# Debug_FeatherWing.net
KiCad netlist of a schematic drawn in EAGLE
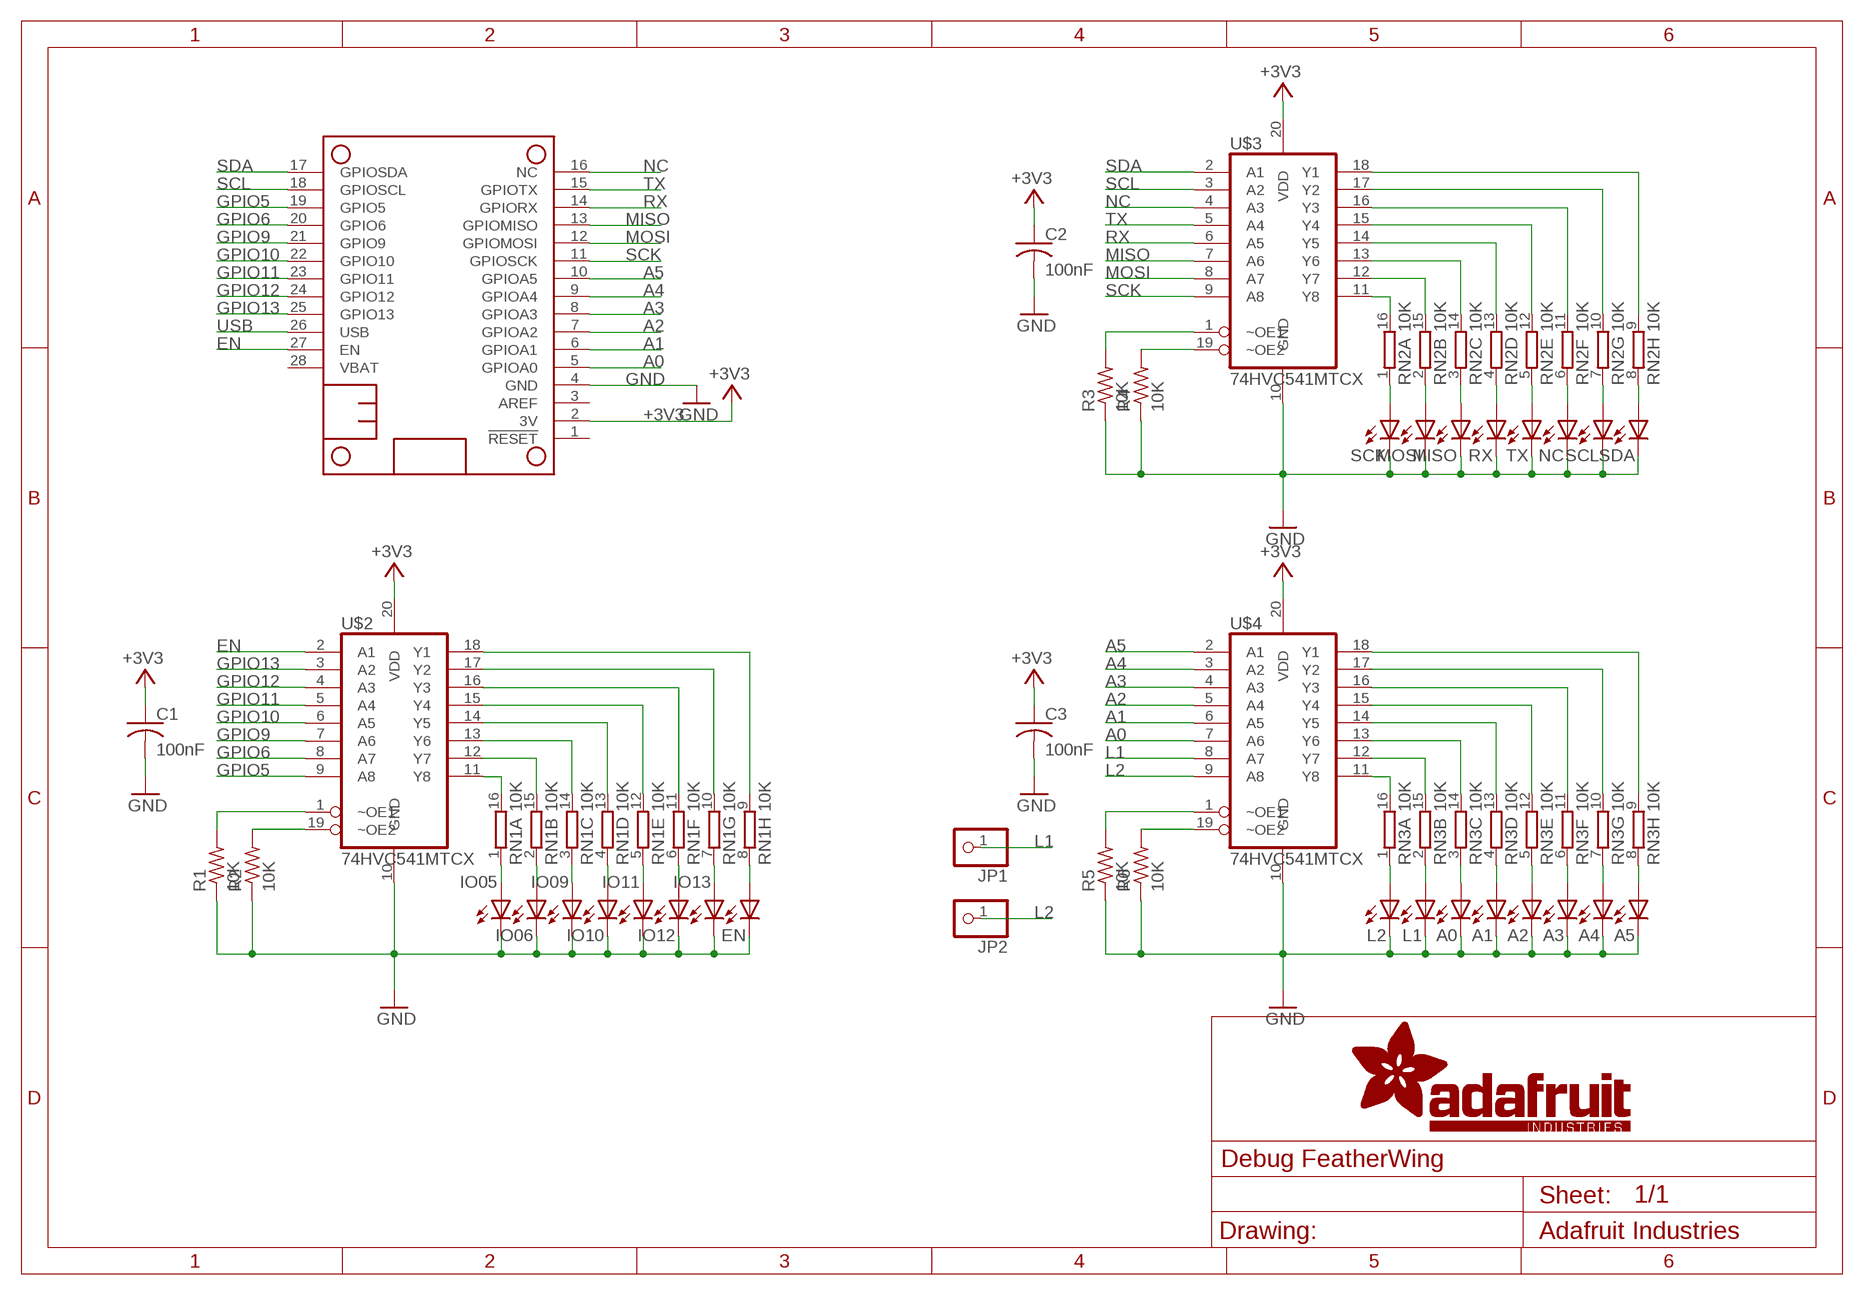
[diagram p0: schematic, sheet 1]

(export (version "E")
  (design (tool "Eeschema 10.0.6"))
  (components
    (comp (ref "A0")
      (value "Green")
      (footprint "eagle-import:CHIPLED_0805")
      (libsource (lib "eagle-import") (part "LEDCHIPLED_0805"))
    )
    (comp (ref "A1")
      (value "Green")
      (footprint "eagle-import:CHIPLED_0805")
      (libsource (lib "eagle-import") (part "LEDCHIPLED_0805"))
    )
    (comp (ref "A2")
      (value "Green")
      (footprint "eagle-import:CHIPLED_0805")
      (libsource (lib "eagle-import") (part "LEDCHIPLED_0805"))
    )
    (comp (ref "A3")
      (value "Green")
      (footprint "eagle-import:CHIPLED_0805")
      (libsource (lib "eagle-import") (part "LEDCHIPLED_0805"))
    )
    (comp (ref "A4")
      (value "Green")
      (footprint "eagle-import:CHIPLED_0805")
      (libsource (lib "eagle-import") (part "LEDCHIPLED_0805"))
    )
    (comp (ref "A5")
      (value "Green")
      (footprint "eagle-import:CHIPLED_0805")
      (libsource (lib "eagle-import") (part "LEDCHIPLED_0805"))
    )
    (comp (ref "C1")
      (value "100nF")
      (footprint "eagle-import:C0805")
      (libsource (lib "eagle-import") (part "C-USC0805"))
    )
    (comp (ref "C2")
      (value "100nF")
      (footprint "eagle-import:C0805")
      (libsource (lib "eagle-import") (part "C-USC0805"))
    )
    (comp (ref "C3")
      (value "100nF")
      (footprint "eagle-import:C0805")
      (libsource (lib "eagle-import") (part "C-USC0805"))
    )
    (comp (ref "EN")
      (value "Green")
      (footprint "eagle-import:CHIPLED_0805")
      (libsource (lib "eagle-import") (part "LEDCHIPLED_0805"))
    )
    (comp (ref "IO05")
      (value "Green")
      (footprint "eagle-import:CHIPLED_0805")
      (libsource (lib "eagle-import") (part "LEDCHIPLED_0805"))
    )
    (comp (ref "IO06")
      (value "Green")
      (footprint "eagle-import:CHIPLED_0805")
      (libsource (lib "eagle-import") (part "LEDCHIPLED_0805"))
    )
    (comp (ref "IO09")
      (value "Green")
      (footprint "eagle-import:CHIPLED_0805")
      (libsource (lib "eagle-import") (part "LEDCHIPLED_0805"))
    )
    (comp (ref "IO10")
      (value "Green")
      (footprint "eagle-import:CHIPLED_0805")
      (libsource (lib "eagle-import") (part "LEDCHIPLED_0805"))
    )
    (comp (ref "IO11")
      (value "Green")
      (footprint "eagle-import:CHIPLED_0805")
      (libsource (lib "eagle-import") (part "LEDCHIPLED_0805"))
    )
    (comp (ref "IO12")
      (value "Green")
      (footprint "eagle-import:CHIPLED_0805")
      (libsource (lib "eagle-import") (part "LEDCHIPLED_0805"))
    )
    (comp (ref "IO13")
      (value "Green")
      (footprint "eagle-import:CHIPLED_0805")
      (libsource (lib "eagle-import") (part "LEDCHIPLED_0805"))
    )
    (comp (ref "JP1")
      (value "PINHD-1X1")
      (footprint "eagle-import:1X01")
      (libsource (lib "eagle-import") (part "PINHD-1X1"))
    )
    (comp (ref "JP2")
      (value "PINHD-1X1")
      (footprint "eagle-import:1X01")
      (libsource (lib "eagle-import") (part "PINHD-1X1"))
    )
    (comp (ref "L1")
      (value "Green")
      (footprint "eagle-import:CHIPLED_0805")
      (libsource (lib "eagle-import") (part "LEDCHIPLED_0805"))
    )
    (comp (ref "L2")
      (value "Green")
      (footprint "eagle-import:CHIPLED_0805")
      (libsource (lib "eagle-import") (part "LEDCHIPLED_0805"))
    )
    (comp (ref "MISO")
      (value "Green")
      (footprint "eagle-import:CHIPLED_0805")
      (libsource (lib "eagle-import") (part "LEDCHIPLED_0805"))
    )
    (comp (ref "MOSI")
      (value "Green")
      (footprint "eagle-import:CHIPLED_0805")
      (libsource (lib "eagle-import") (part "LEDCHIPLED_0805"))
    )
    (comp (ref "MS1")
      (value "FEATHERWING")
      (footprint "eagle-import:FEATHERWING")
      (libsource (lib "eagle-import") (part "FEATHERWING"))
    )
    (comp (ref "NC")
      (value "Green")
      (footprint "eagle-import:CHIPLED_0805")
      (libsource (lib "eagle-import") (part "LEDCHIPLED_0805"))
    )
    (comp (ref "R1")
      (value "10K")
      (footprint "eagle-import:R0805")
      (libsource (lib "eagle-import") (part "R-US_R0805"))
    )
    (comp (ref "R2")
      (value "10K")
      (footprint "eagle-import:R0805")
      (libsource (lib "eagle-import") (part "R-US_R0805"))
    )
    (comp (ref "R3")
      (value "10K")
      (footprint "eagle-import:R0805")
      (libsource (lib "eagle-import") (part "R-US_R0805"))
    )
    (comp (ref "R4")
      (value "10K")
      (footprint "eagle-import:R0805")
      (libsource (lib "eagle-import") (part "R-US_R0805"))
    )
    (comp (ref "R5")
      (value "10K")
      (footprint "eagle-import:R0805")
      (libsource (lib "eagle-import") (part "R-US_R0805"))
    )
    (comp (ref "R6")
      (value "10K")
      (footprint "eagle-import:R0805")
      (libsource (lib "eagle-import") (part "R-US_R0805"))
    )
    (comp (ref "RN1")
      (value "10K")
      (footprint "eagle-import:EXB2HV")
      (libsource (lib "eagle-import") (part "8R-NEXB2HV"))
    )
    (comp (ref "RN2")
      (value "10K")
      (footprint "eagle-import:EXB2HV")
      (libsource (lib "eagle-import") (part "8R-NEXB2HV"))
    )
    (comp (ref "RN3")
      (value "10K")
      (footprint "eagle-import:EXB2HV")
      (libsource (lib "eagle-import") (part "8R-NEXB2HV"))
    )
    (comp (ref "RX")
      (value "Green")
      (footprint "eagle-import:CHIPLED_0805")
      (libsource (lib "eagle-import") (part "LEDCHIPLED_0805"))
    )
    (comp (ref "SCK")
      (value "Green")
      (footprint "eagle-import:CHIPLED_0805")
      (libsource (lib "eagle-import") (part "LEDCHIPLED_0805"))
    )
    (comp (ref "SCL")
      (value "Green")
      (footprint "eagle-import:CHIPLED_0805")
      (libsource (lib "eagle-import") (part "LEDCHIPLED_0805"))
    )
    (comp (ref "SDA")
      (value "Green")
      (footprint "eagle-import:CHIPLED_0805")
      (libsource (lib "eagle-import") (part "LEDCHIPLED_0805"))
    )
    (comp (ref "TX")
      (value "Green")
      (footprint "eagle-import:CHIPLED_0805")
      (libsource (lib "eagle-import") (part "LEDCHIPLED_0805"))
    )
    (comp (ref "U$2")
      (value "74HVC541MTCX")
      (footprint "eagle-import:TSSOP20")
      (libsource (lib "eagle-import") (part "74HVC541MTCX"))
    )
    (comp (ref "U$3")
      (value "74HVC541MTCX")
      (footprint "eagle-import:TSSOP20")
      (libsource (lib "eagle-import") (part "74HVC541MTCX"))
    )
    (comp (ref "U$4")
      (value "74HVC541MTCX")
      (footprint "eagle-import:TSSOP20")
      (libsource (lib "eagle-import") (part "74HVC541MTCX"))
    )
  )
  (nets
    (net (code "1") (name "+3V3") (class "Default")
      (node (ref "C1") (pin "1") (pinfunction "1_1") (pintype "passive"))
      (node (ref "C2") (pin "1") (pinfunction "1_1") (pintype "passive"))
      (node (ref "C3") (pin "1") (pinfunction "1_1") (pintype "passive"))
      (node (ref "MS1") (pin "2") (pinfunction "3V_2") (pintype "power_in"))
      (node (ref "U$2") (pin "20") (pinfunction "VDD_20") (pintype "power_in"))
      (node (ref "U$3") (pin "20") (pinfunction "VDD_20") (pintype "power_in"))
      (node (ref "U$4") (pin "20") (pinfunction "VDD_20") (pintype "power_in"))
    )
    (net (code "2") (name "/A0") (class "Default")
      (node (ref "MS1") (pin "5") (pinfunction "GPIOA0_5") (pintype "bidirectional"))
      (node (ref "U$4") (pin "7") (pinfunction "A6_7") (pintype "input"))
    )
    (net (code "3") (name "/A1") (class "Default")
      (node (ref "MS1") (pin "6") (pinfunction "GPIOA1_6") (pintype "bidirectional"))
      (node (ref "U$4") (pin "6") (pinfunction "A5_6") (pintype "input"))
    )
    (net (code "4") (name "/A2") (class "Default")
      (node (ref "MS1") (pin "7") (pinfunction "GPIOA2_7") (pintype "bidirectional"))
      (node (ref "U$4") (pin "5") (pinfunction "A4_5") (pintype "input"))
    )
    (net (code "5") (name "/A3") (class "Default")
      (node (ref "MS1") (pin "8") (pinfunction "GPIOA3_8") (pintype "bidirectional"))
      (node (ref "U$4") (pin "4") (pinfunction "A3_4") (pintype "input"))
    )
    (net (code "6") (name "/A4") (class "Default")
      (node (ref "MS1") (pin "9") (pinfunction "GPIOA4_9") (pintype "bidirectional"))
      (node (ref "U$4") (pin "3") (pinfunction "A2_3") (pintype "input"))
    )
    (net (code "7") (name "/A5") (class "Default")
      (node (ref "MS1") (pin "10") (pinfunction "GPIOA5_10") (pintype "bidirectional"))
      (node (ref "U$4") (pin "2") (pinfunction "A1_2") (pintype "input"))
    )
    (net (code "8") (name "/EN") (class "Default")
      (node (ref "MS1") (pin "27") (pinfunction "EN_27") (pintype "passive"))
      (node (ref "U$2") (pin "2") (pinfunction "A1_2") (pintype "input"))
    )
    (net (code "9") (name "/GPIO5") (class "Default")
      (node (ref "MS1") (pin "19") (pinfunction "GPIO5_19") (pintype "bidirectional"))
      (node (ref "U$2") (pin "9") (pinfunction "A8_9") (pintype "input"))
    )
    (net (code "10") (name "/GPIO6") (class "Default")
      (node (ref "MS1") (pin "20") (pinfunction "GPIO6_20") (pintype "bidirectional"))
      (node (ref "U$2") (pin "8") (pinfunction "A7_8") (pintype "input"))
    )
    (net (code "11") (name "/GPIO9") (class "Default")
      (node (ref "MS1") (pin "21") (pinfunction "GPIO9_21") (pintype "bidirectional"))
      (node (ref "U$2") (pin "7") (pinfunction "A6_7") (pintype "input"))
    )
    (net (code "12") (name "/GPIO10") (class "Default")
      (node (ref "MS1") (pin "22") (pinfunction "GPIO10_22") (pintype "bidirectional"))
      (node (ref "U$2") (pin "6") (pinfunction "A5_6") (pintype "input"))
    )
    (net (code "13") (name "/GPIO11") (class "Default")
      (node (ref "MS1") (pin "23") (pinfunction "GPIO11_23") (pintype "bidirectional"))
      (node (ref "U$2") (pin "5") (pinfunction "A4_5") (pintype "input"))
    )
    (net (code "14") (name "/GPIO12") (class "Default")
      (node (ref "MS1") (pin "24") (pinfunction "GPIO12_24") (pintype "bidirectional"))
      (node (ref "U$2") (pin "4") (pinfunction "A3_4") (pintype "input"))
    )
    (net (code "15") (name "/GPIO13") (class "Default")
      (node (ref "MS1") (pin "25") (pinfunction "GPIO13_25") (pintype "bidirectional"))
      (node (ref "U$2") (pin "3") (pinfunction "A2_3") (pintype "input"))
    )
    (net (code "16") (name "/L1") (class "Default")
      (node (ref "JP1") (pin "1") (pinfunction "1_1") (pintype "passive"))
      (node (ref "U$4") (pin "8") (pinfunction "A7_8") (pintype "input"))
    )
    (net (code "17") (name "/L2") (class "Default")
      (node (ref "JP2") (pin "1") (pinfunction "1_1") (pintype "passive"))
      (node (ref "U$4") (pin "9") (pinfunction "A8_9") (pintype "input"))
    )
    (net (code "18") (name "/MISO") (class "Default")
      (node (ref "MS1") (pin "13") (pinfunction "GPIOMISO_13") (pintype "bidirectional"))
      (node (ref "U$3") (pin "7") (pinfunction "A6_7") (pintype "input"))
    )
    (net (code "19") (name "/MOSI") (class "Default")
      (node (ref "MS1") (pin "12") (pinfunction "GPIOMOSI_12") (pintype "bidirectional"))
      (node (ref "U$3") (pin "8") (pinfunction "A7_8") (pintype "input"))
    )
    (net (code "20") (name "/NC") (class "Default")
      (node (ref "MS1") (pin "16") (pinfunction "NC_16") (pintype "passive"))
      (node (ref "U$3") (pin "4") (pinfunction "A3_4") (pintype "input"))
    )
    (net (code "21") (name "/RX") (class "Default")
      (node (ref "MS1") (pin "14") (pinfunction "GPIORX_14") (pintype "bidirectional"))
      (node (ref "U$3") (pin "6") (pinfunction "A5_6") (pintype "input"))
    )
    (net (code "22") (name "/SCK") (class "Default")
      (node (ref "MS1") (pin "11") (pinfunction "GPIOSCK_11") (pintype "bidirectional"))
      (node (ref "U$3") (pin "9") (pinfunction "A8_9") (pintype "input"))
    )
    (net (code "23") (name "/SCL") (class "Default")
      (node (ref "MS1") (pin "18") (pinfunction "GPIOSCL_18") (pintype "bidirectional"))
      (node (ref "U$3") (pin "3") (pinfunction "A2_3") (pintype "input"))
    )
    (net (code "24") (name "/SDA") (class "Default")
      (node (ref "MS1") (pin "17") (pinfunction "GPIOSDA_17") (pintype "bidirectional"))
      (node (ref "U$3") (pin "2") (pinfunction "A1_2") (pintype "input"))
    )
    (net (code "25") (name "/TX") (class "Default")
      (node (ref "MS1") (pin "15") (pinfunction "GPIOTX_15") (pintype "bidirectional"))
      (node (ref "U$3") (pin "5") (pinfunction "A4_5") (pintype "input"))
    )
    (net (code "26") (name "/USB") (class "Default")
      (node (ref "MS1") (pin "26") (pinfunction "USB_26") (pintype "power_in"))
    )
    (net (code "27") (name "/VBAT") (class "Default")
      (node (ref "MS1") (pin "28") (pinfunction "VBAT_28") (pintype "power_in"))
    )
    (net (code "28") (name "GND") (class "Default")
      (node (ref "A0") (pin "C") (pinfunction "C_C") (pintype "passive"))
      (node (ref "A1") (pin "C") (pinfunction "C_C") (pintype "passive"))
      (node (ref "A2") (pin "C") (pinfunction "C_C") (pintype "passive"))
      (node (ref "A3") (pin "C") (pinfunction "C_C") (pintype "passive"))
      (node (ref "A4") (pin "C") (pinfunction "C_C") (pintype "passive"))
      (node (ref "A5") (pin "C") (pinfunction "C_C") (pintype "passive"))
      (node (ref "C1") (pin "2") (pinfunction "2_2") (pintype "passive"))
      (node (ref "C2") (pin "2") (pinfunction "2_2") (pintype "passive"))
      (node (ref "C3") (pin "2") (pinfunction "2_2") (pintype "passive"))
      (node (ref "EN") (pin "C") (pinfunction "C_C") (pintype "passive"))
      (node (ref "IO05") (pin "C") (pinfunction "C_C") (pintype "passive"))
      (node (ref "IO06") (pin "C") (pinfunction "C_C") (pintype "passive"))
      (node (ref "IO09") (pin "C") (pinfunction "C_C") (pintype "passive"))
      (node (ref "IO10") (pin "C") (pinfunction "C_C") (pintype "passive"))
      (node (ref "IO11") (pin "C") (pinfunction "C_C") (pintype "passive"))
      (node (ref "IO12") (pin "C") (pinfunction "C_C") (pintype "passive"))
      (node (ref "IO13") (pin "C") (pinfunction "C_C") (pintype "passive"))
      (node (ref "L1") (pin "C") (pinfunction "C_C") (pintype "passive"))
      (node (ref "L2") (pin "C") (pinfunction "C_C") (pintype "passive"))
      (node (ref "MISO") (pin "C") (pinfunction "C_C") (pintype "passive"))
      (node (ref "MOSI") (pin "C") (pinfunction "C_C") (pintype "passive"))
      (node (ref "MS1") (pin "4") (pinfunction "GND_4") (pintype "power_in"))
      (node (ref "NC") (pin "C") (pinfunction "C_C") (pintype "passive"))
      (node (ref "R1") (pin "1") (pinfunction "1_1") (pintype "passive"))
      (node (ref "R2") (pin "1") (pinfunction "1_1") (pintype "passive"))
      (node (ref "R3") (pin "1") (pinfunction "1_1") (pintype "passive"))
      (node (ref "R4") (pin "1") (pinfunction "1_1") (pintype "passive"))
      (node (ref "R5") (pin "1") (pinfunction "1_1") (pintype "passive"))
      (node (ref "R6") (pin "1") (pinfunction "1_1") (pintype "passive"))
      (node (ref "RX") (pin "C") (pinfunction "C_C") (pintype "passive"))
      (node (ref "SCK") (pin "C") (pinfunction "C_C") (pintype "passive"))
      (node (ref "SCL") (pin "C") (pinfunction "C_C") (pintype "passive"))
      (node (ref "SDA") (pin "C") (pinfunction "C_C") (pintype "passive"))
      (node (ref "TX") (pin "C") (pinfunction "C_C") (pintype "passive"))
      (node (ref "U$2") (pin "10") (pinfunction "GND_10") (pintype "power_in"))
      (node (ref "U$3") (pin "10") (pinfunction "GND_10") (pintype "power_in"))
      (node (ref "U$4") (pin "10") (pinfunction "GND_10") (pintype "power_in"))
    )
    (net (code "29") (name "Net-(IO05-PadA)") (class "Default")
      (node (ref "IO05") (pin "A") (pinfunction "A_A") (pintype "passive"))
      (node (ref "RN1") (pin "1") (pinfunction "1_1") (pintype "passive"))
    )
    (net (code "30") (name "Net-(L2-PadA)") (class "Default")
      (node (ref "L2") (pin "A") (pinfunction "A_A") (pintype "passive"))
      (node (ref "RN3") (pin "1") (pinfunction "1_1") (pintype "passive"))
    )
    (net (code "31") (name "Net-(RN1A-2)") (class "Default")
      (node (ref "RN1") (pin "16") (pinfunction "2_16") (pintype "passive"))
      (node (ref "U$2") (pin "11") (pinfunction "Y8_11") (pintype "tri_state"))
    )
    (net (code "32") (name "Net-(RN1B-1)") (class "Default")
      (node (ref "IO06") (pin "A") (pinfunction "A_A") (pintype "passive"))
      (node (ref "RN1") (pin "2") (pinfunction "1_2") (pintype "passive"))
    )
    (net (code "33") (name "Net-(RN1B-2)") (class "Default")
      (node (ref "RN1") (pin "15") (pinfunction "2_15") (pintype "passive"))
      (node (ref "U$2") (pin "12") (pinfunction "Y7_12") (pintype "tri_state"))
    )
    (net (code "34") (name "Net-(RN1C-1)") (class "Default")
      (node (ref "IO09") (pin "A") (pinfunction "A_A") (pintype "passive"))
      (node (ref "RN1") (pin "3") (pinfunction "1_3") (pintype "passive"))
    )
    (net (code "35") (name "Net-(RN1C-2)") (class "Default")
      (node (ref "RN1") (pin "14") (pinfunction "2_14") (pintype "passive"))
      (node (ref "U$2") (pin "13") (pinfunction "Y6_13") (pintype "tri_state"))
    )
    (net (code "36") (name "Net-(RN1D-1)") (class "Default")
      (node (ref "IO10") (pin "A") (pinfunction "A_A") (pintype "passive"))
      (node (ref "RN1") (pin "4") (pinfunction "1_4") (pintype "passive"))
    )
    (net (code "37") (name "Net-(RN1D-2)") (class "Default")
      (node (ref "RN1") (pin "13") (pinfunction "2_13") (pintype "passive"))
      (node (ref "U$2") (pin "14") (pinfunction "Y5_14") (pintype "tri_state"))
    )
    (net (code "38") (name "Net-(RN1E-1)") (class "Default")
      (node (ref "IO11") (pin "A") (pinfunction "A_A") (pintype "passive"))
      (node (ref "RN1") (pin "5") (pinfunction "1_5") (pintype "passive"))
    )
    (net (code "39") (name "Net-(RN1E-2)") (class "Default")
      (node (ref "RN1") (pin "12") (pinfunction "2_12") (pintype "passive"))
      (node (ref "U$2") (pin "15") (pinfunction "Y4_15") (pintype "tri_state"))
    )
    (net (code "40") (name "Net-(RN1F-1)") (class "Default")
      (node (ref "IO12") (pin "A") (pinfunction "A_A") (pintype "passive"))
      (node (ref "RN1") (pin "6") (pinfunction "1_6") (pintype "passive"))
    )
    (net (code "41") (name "Net-(RN1F-2)") (class "Default")
      (node (ref "RN1") (pin "11") (pinfunction "2_11") (pintype "passive"))
      (node (ref "U$2") (pin "16") (pinfunction "Y3_16") (pintype "tri_state"))
    )
    (net (code "42") (name "Net-(RN1G-1)") (class "Default")
      (node (ref "IO13") (pin "A") (pinfunction "A_A") (pintype "passive"))
      (node (ref "RN1") (pin "7") (pinfunction "1_7") (pintype "passive"))
    )
    (net (code "43") (name "Net-(RN1G-2)") (class "Default")
      (node (ref "RN1") (pin "10") (pinfunction "2_10") (pintype "passive"))
      (node (ref "U$2") (pin "17") (pinfunction "Y2_17") (pintype "tri_state"))
    )
    (net (code "44") (name "Net-(RN1H-1)") (class "Default")
      (node (ref "EN") (pin "A") (pinfunction "A_A") (pintype "passive"))
      (node (ref "RN1") (pin "8") (pinfunction "1_8") (pintype "passive"))
    )
    (net (code "45") (name "Net-(RN1H-2)") (class "Default")
      (node (ref "RN1") (pin "9") (pinfunction "2_9") (pintype "passive"))
      (node (ref "U$2") (pin "18") (pinfunction "Y1_18") (pintype "tri_state"))
    )
    (net (code "46") (name "Net-(RN2-Pad1)") (class "Default")
      (node (ref "RN2") (pin "1") (pinfunction "1_1") (pintype "passive"))
      (node (ref "SCK") (pin "A") (pinfunction "A_A") (pintype "passive"))
    )
    (net (code "47") (name "Net-(RN2A-2)") (class "Default")
      (node (ref "RN2") (pin "16") (pinfunction "2_16") (pintype "passive"))
      (node (ref "U$3") (pin "11") (pinfunction "Y8_11") (pintype "tri_state"))
    )
    (net (code "48") (name "Net-(RN2B-1)") (class "Default")
      (node (ref "MOSI") (pin "A") (pinfunction "A_A") (pintype "passive"))
      (node (ref "RN2") (pin "2") (pinfunction "1_2") (pintype "passive"))
    )
    (net (code "49") (name "Net-(RN2B-2)") (class "Default")
      (node (ref "RN2") (pin "15") (pinfunction "2_15") (pintype "passive"))
      (node (ref "U$3") (pin "12") (pinfunction "Y7_12") (pintype "tri_state"))
    )
    (net (code "50") (name "Net-(RN2C-1)") (class "Default")
      (node (ref "MISO") (pin "A") (pinfunction "A_A") (pintype "passive"))
      (node (ref "RN2") (pin "3") (pinfunction "1_3") (pintype "passive"))
    )
    (net (code "51") (name "Net-(RN2C-2)") (class "Default")
      (node (ref "RN2") (pin "14") (pinfunction "2_14") (pintype "passive"))
      (node (ref "U$3") (pin "13") (pinfunction "Y6_13") (pintype "tri_state"))
    )
    (net (code "52") (name "Net-(RN2D-1)") (class "Default")
      (node (ref "RN2") (pin "4") (pinfunction "1_4") (pintype "passive"))
      (node (ref "RX") (pin "A") (pinfunction "A_A") (pintype "passive"))
    )
    (net (code "53") (name "Net-(RN2D-2)") (class "Default")
      (node (ref "RN2") (pin "13") (pinfunction "2_13") (pintype "passive"))
      (node (ref "U$3") (pin "14") (pinfunction "Y5_14") (pintype "tri_state"))
    )
    (net (code "54") (name "Net-(RN2E-1)") (class "Default")
      (node (ref "RN2") (pin "5") (pinfunction "1_5") (pintype "passive"))
      (node (ref "TX") (pin "A") (pinfunction "A_A") (pintype "passive"))
    )
    (net (code "55") (name "Net-(RN2E-2)") (class "Default")
      (node (ref "RN2") (pin "12") (pinfunction "2_12") (pintype "passive"))
      (node (ref "U$3") (pin "15") (pinfunction "Y4_15") (pintype "tri_state"))
    )
    (net (code "56") (name "Net-(RN2F-1)") (class "Default")
      (node (ref "NC") (pin "A") (pinfunction "A_A") (pintype "passive"))
      (node (ref "RN2") (pin "6") (pinfunction "1_6") (pintype "passive"))
    )
    (net (code "57") (name "Net-(RN2F-2)") (class "Default")
      (node (ref "RN2") (pin "11") (pinfunction "2_11") (pintype "passive"))
      (node (ref "U$3") (pin "16") (pinfunction "Y3_16") (pintype "tri_state"))
    )
    (net (code "58") (name "Net-(RN2G-1)") (class "Default")
      (node (ref "RN2") (pin "7") (pinfunction "1_7") (pintype "passive"))
      (node (ref "SCL") (pin "A") (pinfunction "A_A") (pintype "passive"))
    )
    (net (code "59") (name "Net-(RN2G-2)") (class "Default")
      (node (ref "RN2") (pin "10") (pinfunction "2_10") (pintype "passive"))
      (node (ref "U$3") (pin "17") (pinfunction "Y2_17") (pintype "tri_state"))
    )
    (net (code "60") (name "Net-(RN2H-1)") (class "Default")
      (node (ref "RN2") (pin "8") (pinfunction "1_8") (pintype "passive"))
      (node (ref "SDA") (pin "A") (pinfunction "A_A") (pintype "passive"))
    )
    (net (code "61") (name "Net-(RN2H-2)") (class "Default")
      (node (ref "RN2") (pin "9") (pinfunction "2_9") (pintype "passive"))
      (node (ref "U$3") (pin "18") (pinfunction "Y1_18") (pintype "tri_state"))
    )
    (net (code "62") (name "Net-(RN3A-2)") (class "Default")
      (node (ref "RN3") (pin "16") (pinfunction "2_16") (pintype "passive"))
      (node (ref "U$4") (pin "11") (pinfunction "Y8_11") (pintype "tri_state"))
    )
    (net (code "63") (name "Net-(RN3B-1)") (class "Default")
      (node (ref "L1") (pin "A") (pinfunction "A_A") (pintype "passive"))
      (node (ref "RN3") (pin "2") (pinfunction "1_2") (pintype "passive"))
    )
    (net (code "64") (name "Net-(RN3B-2)") (class "Default")
      (node (ref "RN3") (pin "15") (pinfunction "2_15") (pintype "passive"))
      (node (ref "U$4") (pin "12") (pinfunction "Y7_12") (pintype "tri_state"))
    )
    (net (code "65") (name "Net-(RN3C-1)") (class "Default")
      (node (ref "A0") (pin "A") (pinfunction "A_A") (pintype "passive"))
      (node (ref "RN3") (pin "3") (pinfunction "1_3") (pintype "passive"))
    )
    (net (code "66") (name "Net-(RN3C-2)") (class "Default")
      (node (ref "RN3") (pin "14") (pinfunction "2_14") (pintype "passive"))
      (node (ref "U$4") (pin "13") (pinfunction "Y6_13") (pintype "tri_state"))
    )
    (net (code "67") (name "Net-(RN3D-1)") (class "Default")
      (node (ref "A1") (pin "A") (pinfunction "A_A") (pintype "passive"))
      (node (ref "RN3") (pin "4") (pinfunction "1_4") (pintype "passive"))
    )
    (net (code "68") (name "Net-(RN3D-2)") (class "Default")
      (node (ref "RN3") (pin "13") (pinfunction "2_13") (pintype "passive"))
      (node (ref "U$4") (pin "14") (pinfunction "Y5_14") (pintype "tri_state"))
    )
    (net (code "69") (name "Net-(RN3E-1)") (class "Default")
      (node (ref "A2") (pin "A") (pinfunction "A_A") (pintype "passive"))
      (node (ref "RN3") (pin "5") (pinfunction "1_5") (pintype "passive"))
    )
    (net (code "70") (name "Net-(RN3E-2)") (class "Default")
      (node (ref "RN3") (pin "12") (pinfunction "2_12") (pintype "passive"))
      (node (ref "U$4") (pin "15") (pinfunction "Y4_15") (pintype "tri_state"))
    )
    (net (code "71") (name "Net-(RN3F-1)") (class "Default")
      (node (ref "A3") (pin "A") (pinfunction "A_A") (pintype "passive"))
      (node (ref "RN3") (pin "6") (pinfunction "1_6") (pintype "passive"))
    )
    (net (code "72") (name "Net-(RN3F-2)") (class "Default")
      (node (ref "RN3") (pin "11") (pinfunction "2_11") (pintype "passive"))
      (node (ref "U$4") (pin "16") (pinfunction "Y3_16") (pintype "tri_state"))
    )
    (net (code "73") (name "Net-(RN3G-1)") (class "Default")
      (node (ref "A4") (pin "A") (pinfunction "A_A") (pintype "passive"))
      (node (ref "RN3") (pin "7") (pinfunction "1_7") (pintype "passive"))
    )
    (net (code "74") (name "Net-(RN3G-2)") (class "Default")
      (node (ref "RN3") (pin "10") (pinfunction "2_10") (pintype "passive"))
      (node (ref "U$4") (pin "17") (pinfunction "Y2_17") (pintype "tri_state"))
    )
    (net (code "75") (name "Net-(RN3H-1)") (class "Default")
      (node (ref "A5") (pin "A") (pinfunction "A_A") (pintype "passive"))
      (node (ref "RN3") (pin "8") (pinfunction "1_8") (pintype "passive"))
    )
    (net (code "76") (name "Net-(RN3H-2)") (class "Default")
      (node (ref "RN3") (pin "9") (pinfunction "2_9") (pintype "passive"))
      (node (ref "U$4") (pin "18") (pinfunction "Y1_18") (pintype "tri_state"))
    )
    (net (code "77") (name "Net-(U$2-~{OE1})") (class "Default")
      (node (ref "R1") (pin "2") (pinfunction "2_2") (pintype "passive"))
      (node (ref "U$2") (pin "1") (pinfunction "~{OE1}_1") (pintype "input"))
    )
    (net (code "78") (name "Net-(U$2-~{OE2})") (class "Default")
      (node (ref "R2") (pin "2") (pinfunction "2_2") (pintype "passive"))
      (node (ref "U$2") (pin "19") (pinfunction "~{OE2}_19") (pintype "input"))
    )
    (net (code "79") (name "Net-(U$3-~{OE1})") (class "Default")
      (node (ref "R3") (pin "2") (pinfunction "2_2") (pintype "passive"))
      (node (ref "U$3") (pin "1") (pinfunction "~{OE1}_1") (pintype "input"))
    )
    (net (code "80") (name "Net-(U$3-~{OE2})") (class "Default")
      (node (ref "R4") (pin "2") (pinfunction "2_2") (pintype "passive"))
      (node (ref "U$3") (pin "19") (pinfunction "~{OE2}_19") (pintype "input"))
    )
    (net (code "81") (name "Net-(U$4-~{OE1})") (class "Default")
      (node (ref "R5") (pin "2") (pinfunction "2_2") (pintype "passive"))
      (node (ref "U$4") (pin "1") (pinfunction "~{OE1}_1") (pintype "input"))
    )
    (net (code "82") (name "Net-(U$4-~{OE2})") (class "Default")
      (node (ref "R6") (pin "2") (pinfunction "2_2") (pintype "passive"))
      (node (ref "U$4") (pin "19") (pinfunction "~{OE2}_19") (pintype "input"))
    )
    (net (code "83") (name "unconnected-(MS1-AREF-Pad3)") (class "Default")
      (node (ref "MS1") (pin "3") (pinfunction "AREF_3") (pintype "passive"))
    )
    (net (code "84") (name "unconnected-(MS1-~{RESET}-Pad1)") (class "Default")
      (node (ref "MS1") (pin "1") (pinfunction "~{RESET}_1") (pintype "input"))
    )
  )
)
